# ADC_part3.net
KiCad netlist of a schematic drawn in Altium Designer
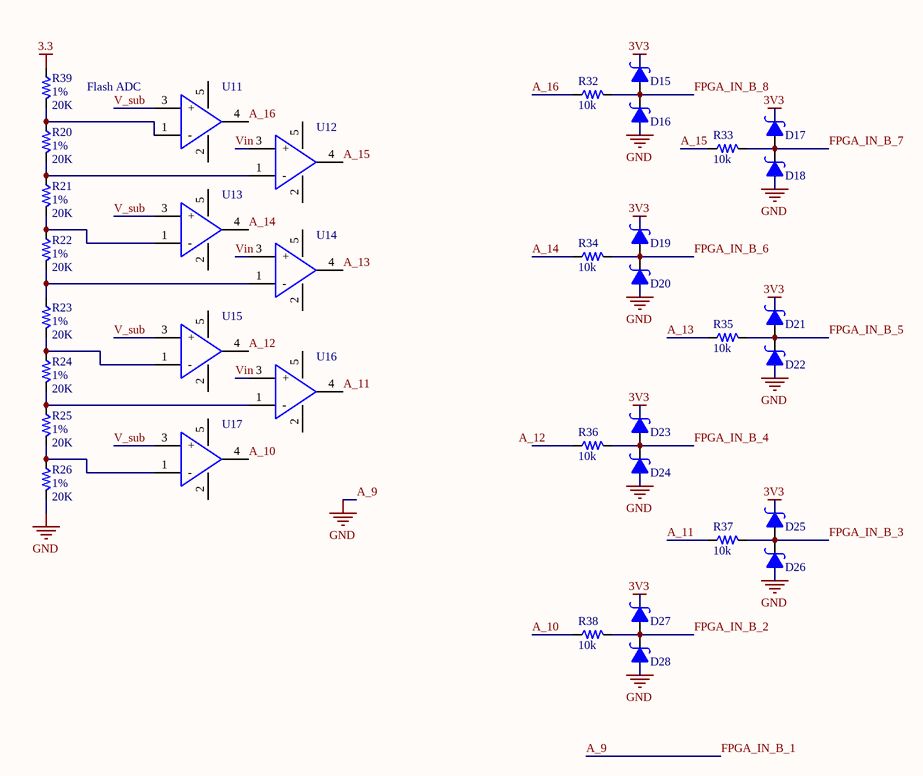
[diagram p0: ADC_part3.SchDoc]

(export (version "E")
  (design (tool "Eeschema 10.0.6"))
  (components
    (comp (ref "D15")
      (value "ONSEMI_MBRM110LT1G")
      (footprint "ON Semi Schottky Diode - MBRM110LT1G")
      (description "DIODE SCHOTTKY 10V 1A")
      (libsource (lib "ON Semi Schottky Diode") (part "ONSEMI_MBRM110LT1G"))
    )
    (comp (ref "D16")
      (value "ONSEMI_MBRM110LT1G")
      (footprint "ON Semi Schottky Diode - MBRM110LT1G")
      (description "DIODE SCHOTTKY 10V 1A")
      (libsource (lib "ON Semi Schottky Diode") (part "ONSEMI_MBRM110LT1G"))
    )
    (comp (ref "D17")
      (value "ONSEMI_MBRM110LT1G")
      (footprint "ON Semi Schottky Diode - MBRM110LT1G")
      (description "DIODE SCHOTTKY 10V 1A")
      (libsource (lib "ON Semi Schottky Diode") (part "ONSEMI_MBRM110LT1G"))
    )
    (comp (ref "D18")
      (value "ONSEMI_MBRM110LT1G")
      (footprint "ON Semi Schottky Diode - MBRM110LT1G")
      (description "DIODE SCHOTTKY 10V 1A")
      (libsource (lib "ON Semi Schottky Diode") (part "ONSEMI_MBRM110LT1G"))
    )
    (comp (ref "D19")
      (value "ONSEMI_MBRM110LT1G")
      (footprint "ON Semi Schottky Diode - MBRM110LT1G")
      (description "DIODE SCHOTTKY 10V 1A")
      (libsource (lib "ON Semi Schottky Diode") (part "ONSEMI_MBRM110LT1G"))
    )
    (comp (ref "D20")
      (value "ONSEMI_MBRM110LT1G")
      (footprint "ON Semi Schottky Diode - MBRM110LT1G")
      (description "DIODE SCHOTTKY 10V 1A")
      (libsource (lib "ON Semi Schottky Diode") (part "ONSEMI_MBRM110LT1G"))
    )
    (comp (ref "D21")
      (value "ONSEMI_MBRM110LT1G")
      (footprint "ON Semi Schottky Diode - MBRM110LT1G")
      (description "DIODE SCHOTTKY 10V 1A")
      (libsource (lib "ON Semi Schottky Diode") (part "ONSEMI_MBRM110LT1G"))
    )
    (comp (ref "D22")
      (value "ONSEMI_MBRM110LT1G")
      (footprint "ON Semi Schottky Diode - MBRM110LT1G")
      (description "DIODE SCHOTTKY 10V 1A")
      (libsource (lib "ON Semi Schottky Diode") (part "ONSEMI_MBRM110LT1G"))
    )
    (comp (ref "D23")
      (value "ONSEMI_MBRM110LT1G")
      (footprint "ON Semi Schottky Diode - MBRM110LT1G")
      (description "DIODE SCHOTTKY 10V 1A")
      (libsource (lib "ON Semi Schottky Diode") (part "ONSEMI_MBRM110LT1G"))
    )
    (comp (ref "D24")
      (value "ONSEMI_MBRM110LT1G")
      (footprint "ON Semi Schottky Diode - MBRM110LT1G")
      (description "DIODE SCHOTTKY 10V 1A")
      (libsource (lib "ON Semi Schottky Diode") (part "ONSEMI_MBRM110LT1G"))
    )
    (comp (ref "D25")
      (value "ONSEMI_MBRM110LT1G")
      (footprint "ON Semi Schottky Diode - MBRM110LT1G")
      (description "DIODE SCHOTTKY 10V 1A")
      (libsource (lib "ON Semi Schottky Diode") (part "ONSEMI_MBRM110LT1G"))
    )
    (comp (ref "D26")
      (value "ONSEMI_MBRM110LT1G")
      (footprint "ON Semi Schottky Diode - MBRM110LT1G")
      (description "DIODE SCHOTTKY 10V 1A")
      (libsource (lib "ON Semi Schottky Diode") (part "ONSEMI_MBRM110LT1G"))
    )
    (comp (ref "D27")
      (value "ONSEMI_MBRM110LT1G")
      (footprint "ON Semi Schottky Diode - MBRM110LT1G")
      (description "DIODE SCHOTTKY 10V 1A")
      (libsource (lib "ON Semi Schottky Diode") (part "ONSEMI_MBRM110LT1G"))
    )
    (comp (ref "D28")
      (value "ONSEMI_MBRM110LT1G")
      (footprint "ON Semi Schottky Diode - MBRM110LT1G")
      (description "DIODE SCHOTTKY 10V 1A")
      (libsource (lib "ON Semi Schottky Diode") (part "ONSEMI_MBRM110LT1G"))
    )
    (comp (ref "R20")
      (value "20K")
      (footprint "PCB_GENERIC_SMD_0603")
      (description "RES 0603 10K 1% 100mW")
      (fields
        (field (name "POWER") "100mW")
        (field (name "TOLERANCE") "1%")
        (field (name "Comment") "R060-00103-01")
      )
      (libsource (lib "RES") (part "R060-00103-01"))
    )
    (comp (ref "R21")
      (value "20K")
      (footprint "PCB_GENERIC_SMD_0603")
      (description "RES 0603 10K 1% 100mW")
      (fields
        (field (name "POWER") "100mW")
        (field (name "TOLERANCE") "1%")
        (field (name "Comment") "R060-00103-01")
      )
      (libsource (lib "RES") (part "R060-00103-01"))
    )
    (comp (ref "R22")
      (value "20K")
      (footprint "PCB_GENERIC_SMD_0603")
      (description "RES 0603 10K 1% 100mW")
      (fields
        (field (name "POWER") "100mW")
        (field (name "TOLERANCE") "1%")
        (field (name "Comment") "R060-00103-01")
      )
      (libsource (lib "RES") (part "R060-00103-01"))
    )
    (comp (ref "R23")
      (value "20K")
      (footprint "PCB_GENERIC_SMD_0603")
      (description "RES 0603 10K 1% 100mW")
      (fields
        (field (name "POWER") "100mW")
        (field (name "TOLERANCE") "1%")
        (field (name "Comment") "R060-00103-01")
      )
      (libsource (lib "RES") (part "R060-00103-01"))
    )
    (comp (ref "R24")
      (value "20K")
      (footprint "PCB_GENERIC_SMD_0603")
      (description "RES 0603 10K 1% 100mW")
      (fields
        (field (name "POWER") "100mW")
        (field (name "TOLERANCE") "1%")
        (field (name "Comment") "R060-00103-01")
      )
      (libsource (lib "RES") (part "R060-00103-01"))
    )
    (comp (ref "R25")
      (value "20K")
      (footprint "PCB_GENERIC_SMD_0603")
      (description "RES 0603 10K 1% 100mW")
      (fields
        (field (name "POWER") "100mW")
        (field (name "TOLERANCE") "1%")
        (field (name "Comment") "R060-00103-01")
      )
      (libsource (lib "RES") (part "R060-00103-01"))
    )
    (comp (ref "R26")
      (value "20K")
      (footprint "PCB_GENERIC_SMD_0603")
      (description "RES 0603 10K 1% 100mW")
      (fields
        (field (name "POWER") "100mW")
        (field (name "TOLERANCE") "1%")
        (field (name "Comment") "R060-00103-01")
      )
      (libsource (lib "RES") (part "R060-00103-01"))
    )
    (comp (ref "R32")
      (value "10k")
      (footprint "PCB_GENERIC_SMD_0603")
      (description "RES 0603 100ohm 5% 63mW")
      (fields (field (name "TOLERANCE") "5%") (field (name "POWER") "63mW"))
      (libsource (lib "RES") (part "R060-00101-05"))
    )
    (comp (ref "R33")
      (value "10k")
      (footprint "PCB_GENERIC_SMD_0603")
      (description "RES 0603 100ohm 5% 63mW")
      (fields (field (name "TOLERANCE") "5%") (field (name "POWER") "63mW"))
      (libsource (lib "RES") (part "R060-00101-05"))
    )
    (comp (ref "R34")
      (value "10k")
      (footprint "PCB_GENERIC_SMD_0603")
      (description "RES 0603 100ohm 5% 63mW")
      (fields (field (name "TOLERANCE") "5%") (field (name "POWER") "63mW"))
      (libsource (lib "RES") (part "R060-00101-05"))
    )
    (comp (ref "R35")
      (value "10k")
      (footprint "PCB_GENERIC_SMD_0603")
      (description "RES 0603 100ohm 5% 63mW")
      (fields (field (name "TOLERANCE") "5%") (field (name "POWER") "63mW"))
      (libsource (lib "RES") (part "R060-00101-05"))
    )
    (comp (ref "R36")
      (value "10k")
      (footprint "PCB_GENERIC_SMD_0603")
      (description "RES 0603 100ohm 5% 63mW")
      (fields (field (name "TOLERANCE") "5%") (field (name "POWER") "63mW"))
      (libsource (lib "RES") (part "R060-00101-05"))
    )
    (comp (ref "R37")
      (value "10k")
      (footprint "PCB_GENERIC_SMD_0603")
      (description "RES 0603 100ohm 5% 63mW")
      (fields (field (name "TOLERANCE") "5%") (field (name "POWER") "63mW"))
      (libsource (lib "RES") (part "R060-00101-05"))
    )
    (comp (ref "R38")
      (value "10k")
      (footprint "PCB_GENERIC_SMD_0603")
      (description "RES 0603 100ohm 5% 63mW")
      (fields (field (name "TOLERANCE") "5%") (field (name "POWER") "63mW"))
      (libsource (lib "RES") (part "R060-00101-05"))
    )
    (comp (ref "R39")
      (value "20K")
      (footprint "PCB_GENERIC_SMD_0603")
      (description "RES 0603 10K 1% 100mW")
      (fields
        (field (name "POWER") "100mW")
        (field (name "TOLERANCE") "1%")
        (field (name "Comment") "R060-00103-01")
      )
      (libsource (lib "RES") (part "R060-00103-01"))
    )
    (comp (ref "U11")
      (value "AP331A")
      (footprint "SOT95P285X130-5N")
      (description "Single Channel Comparator, Open Drain, SC-74A/SOT-753")
      (libsource (lib "Op_Amp") (part "AP331A"))
    )
    (comp (ref "U12")
      (value "AP331A")
      (footprint "SOT95P285X130-5N")
      (description "Single Channel Comparator, Open Drain, SC-74A/SOT-753")
      (libsource (lib "Op_Amp") (part "AP331A"))
    )
    (comp (ref "U13")
      (value "AP331A")
      (footprint "SOT95P285X130-5N")
      (description "Single Channel Comparator, Open Drain, SC-74A/SOT-753")
      (libsource (lib "Op_Amp") (part "AP331A"))
    )
    (comp (ref "U14")
      (value "AP331A")
      (footprint "SOT95P285X130-5N")
      (description "Single Channel Comparator, Open Drain, SC-74A/SOT-753")
      (libsource (lib "Op_Amp") (part "AP331A"))
    )
    (comp (ref "U15")
      (value "AP331A")
      (footprint "SOT95P285X130-5N")
      (description "Single Channel Comparator, Open Drain, SC-74A/SOT-753")
      (libsource (lib "Op_Amp") (part "AP331A"))
    )
    (comp (ref "U16")
      (value "AP331A")
      (footprint "SOT95P285X130-5N")
      (description "Single Channel Comparator, Open Drain, SC-74A/SOT-753")
      (libsource (lib "Op_Amp") (part "AP331A"))
    )
    (comp (ref "U17")
      (value "AP331A")
      (footprint "SOT95P285X130-5N")
      (description "Single Channel Comparator, Open Drain, SC-74A/SOT-753")
      (libsource (lib "Op_Amp") (part "AP331A"))
    )
  )
  (nets
    (net (code "1") (name "/A_10") (class "Default")
      (node (ref "R38") (pin "1") (pinfunction "1_1") (pintype "passive"))
      (node (ref "U17") (pin "4") (pinfunction "VOUT_4") (pintype "passive"))
    )
    (net (code "2") (name "/A_11") (class "Default")
      (node (ref "R37") (pin "1") (pinfunction "1_1") (pintype "passive"))
      (node (ref "U16") (pin "4") (pinfunction "VOUT_4") (pintype "passive"))
    )
    (net (code "3") (name "/A_12") (class "Default")
      (node (ref "U15") (pin "4") (pinfunction "VOUT_4") (pintype "passive"))
    )
    (net (code "4") (name "/A_13") (class "Default")
      (node (ref "R35") (pin "1") (pinfunction "1_1") (pintype "passive"))
      (node (ref "U14") (pin "4") (pinfunction "VOUT_4") (pintype "passive"))
    )
    (net (code "5") (name "/A_14") (class "Default")
      (node (ref "R34") (pin "1") (pinfunction "1_1") (pintype "passive"))
      (node (ref "U13") (pin "4") (pinfunction "VOUT_4") (pintype "passive"))
    )
    (net (code "6") (name "/A_15") (class "Default")
      (node (ref "R33") (pin "1") (pinfunction "1_1") (pintype "passive"))
      (node (ref "U12") (pin "4") (pinfunction "VOUT_4") (pintype "passive"))
    )
    (net (code "7") (name "/A_16") (class "Default")
      (node (ref "R32") (pin "1") (pinfunction "1_1") (pintype "passive"))
      (node (ref "U11") (pin "4") (pinfunction "VOUT_4") (pintype "passive"))
    )
    (net (code "8") (name "/FPGA_IN_B_2") (class "Default")
      (node (ref "D27") (pin "2") (pinfunction "2_2") (pintype "passive"))
      (node (ref "D28") (pin "1") (pinfunction "1_1") (pintype "passive"))
      (node (ref "R38") (pin "2") (pinfunction "2_2") (pintype "passive"))
    )
    (net (code "9") (name "/FPGA_IN_B_3") (class "Default")
      (node (ref "D25") (pin "2") (pinfunction "2_2") (pintype "passive"))
      (node (ref "D26") (pin "1") (pinfunction "1_1") (pintype "passive"))
      (node (ref "R37") (pin "2") (pinfunction "2_2") (pintype "passive"))
    )
    (net (code "10") (name "/FPGA_IN_B_4") (class "Default")
      (node (ref "D23") (pin "2") (pinfunction "2_2") (pintype "passive"))
      (node (ref "D24") (pin "1") (pinfunction "1_1") (pintype "passive"))
      (node (ref "R36") (pin "2") (pinfunction "2_2") (pintype "passive"))
    )
    (net (code "11") (name "/FPGA_IN_B_5") (class "Default")
      (node (ref "D21") (pin "2") (pinfunction "2_2") (pintype "passive"))
      (node (ref "D22") (pin "1") (pinfunction "1_1") (pintype "passive"))
      (node (ref "R35") (pin "2") (pinfunction "2_2") (pintype "passive"))
    )
    (net (code "12") (name "/FPGA_IN_B_6") (class "Default")
      (node (ref "D19") (pin "2") (pinfunction "2_2") (pintype "passive"))
      (node (ref "D20") (pin "1") (pinfunction "1_1") (pintype "passive"))
      (node (ref "R34") (pin "2") (pinfunction "2_2") (pintype "passive"))
    )
    (net (code "13") (name "/FPGA_IN_B_7") (class "Default")
      (node (ref "D17") (pin "2") (pinfunction "2_2") (pintype "passive"))
      (node (ref "D18") (pin "1") (pinfunction "1_1") (pintype "passive"))
      (node (ref "R33") (pin "2") (pinfunction "2_2") (pintype "passive"))
    )
    (net (code "14") (name "/FPGA_IN_B_8") (class "Default")
      (node (ref "D15") (pin "2") (pinfunction "2_2") (pintype "passive"))
      (node (ref "D16") (pin "1") (pinfunction "1_1") (pintype "passive"))
      (node (ref "R32") (pin "2") (pinfunction "2_2") (pintype "passive"))
    )
    (net (code "15") (name "/V_sub") (class "Default")
      (node (ref "U11") (pin "3") (pinfunction "+_3") (pintype "passive"))
      (node (ref "U13") (pin "3") (pinfunction "+_3") (pintype "passive"))
      (node (ref "U15") (pin "3") (pinfunction "+_3") (pintype "passive"))
      (node (ref "U17") (pin "3") (pinfunction "+_3") (pintype "passive"))
    )
    (net (code "16") (name "/Vin") (class "Default")
      (node (ref "U12") (pin "3") (pinfunction "+_3") (pintype "passive"))
      (node (ref "U14") (pin "3") (pinfunction "+_3") (pintype "passive"))
      (node (ref "U16") (pin "3") (pinfunction "+_3") (pintype "passive"))
    )
    (net (code "17") (name "3.3") (class "Default")
      (node (ref "R39") (pin "1") (pinfunction "1_1") (pintype "passive"))
    )
    (net (code "18") (name "3V3") (class "Default")
      (node (ref "D15") (pin "1") (pinfunction "1_1") (pintype "passive"))
      (node (ref "D17") (pin "1") (pinfunction "1_1") (pintype "passive"))
      (node (ref "D19") (pin "1") (pinfunction "1_1") (pintype "passive"))
      (node (ref "D21") (pin "1") (pinfunction "1_1") (pintype "passive"))
      (node (ref "D23") (pin "1") (pinfunction "1_1") (pintype "passive"))
      (node (ref "D25") (pin "1") (pinfunction "1_1") (pintype "passive"))
      (node (ref "D27") (pin "1") (pinfunction "1_1") (pintype "passive"))
    )
    (net (code "19") (name "GND") (class "Default")
      (node (ref "D16") (pin "2") (pinfunction "2_2") (pintype "passive"))
      (node (ref "D18") (pin "2") (pinfunction "2_2") (pintype "passive"))
      (node (ref "D20") (pin "2") (pinfunction "2_2") (pintype "passive"))
      (node (ref "D22") (pin "2") (pinfunction "2_2") (pintype "passive"))
      (node (ref "D24") (pin "2") (pinfunction "2_2") (pintype "passive"))
      (node (ref "D26") (pin "2") (pinfunction "2_2") (pintype "passive"))
      (node (ref "D28") (pin "2") (pinfunction "2_2") (pintype "passive"))
      (node (ref "R26") (pin "2") (pinfunction "2_2") (pintype "passive"))
    )
    (net (code "20") (name "Net-(U11--)") (class "Default")
      (node (ref "R20") (pin "1") (pinfunction "1_1") (pintype "passive"))
      (node (ref "R39") (pin "2") (pinfunction "2_2") (pintype "passive"))
      (node (ref "U11") (pin "1") (pinfunction "-_1") (pintype "passive"))
    )
    (net (code "21") (name "Net-(U12--)") (class "Default")
      (node (ref "R20") (pin "2") (pinfunction "2_2") (pintype "passive"))
      (node (ref "R21") (pin "1") (pinfunction "1_1") (pintype "passive"))
      (node (ref "U12") (pin "1") (pinfunction "-_1") (pintype "passive"))
    )
    (net (code "22") (name "Net-(U13--)") (class "Default")
      (node (ref "R21") (pin "2") (pinfunction "2_2") (pintype "passive"))
      (node (ref "R22") (pin "1") (pinfunction "1_1") (pintype "passive"))
      (node (ref "U13") (pin "1") (pinfunction "-_1") (pintype "passive"))
    )
    (net (code "23") (name "Net-(U14--)") (class "Default")
      (node (ref "R22") (pin "2") (pinfunction "2_2") (pintype "passive"))
      (node (ref "R23") (pin "1") (pinfunction "1_1") (pintype "passive"))
      (node (ref "U14") (pin "1") (pinfunction "-_1") (pintype "passive"))
    )
    (net (code "24") (name "Net-(U15--)") (class "Default")
      (node (ref "R23") (pin "2") (pinfunction "2_2") (pintype "passive"))
      (node (ref "R24") (pin "1") (pinfunction "1_1") (pintype "passive"))
      (node (ref "U15") (pin "1") (pinfunction "-_1") (pintype "passive"))
    )
    (net (code "25") (name "Net-(U16--)") (class "Default")
      (node (ref "R24") (pin "2") (pinfunction "2_2") (pintype "passive"))
      (node (ref "R25") (pin "1") (pinfunction "1_1") (pintype "passive"))
      (node (ref "U16") (pin "1") (pinfunction "-_1") (pintype "passive"))
    )
    (net (code "26") (name "Net-(U17--)") (class "Default")
      (node (ref "R25") (pin "2") (pinfunction "2_2") (pintype "passive"))
      (node (ref "R26") (pin "1") (pinfunction "1_1") (pintype "passive"))
      (node (ref "U17") (pin "1") (pinfunction "-_1") (pintype "passive"))
    )
    (net (code "27") (name "unconnected-(R36-Pad1)") (class "Default")
      (node (ref "R36") (pin "1") (pinfunction "1_1") (pintype "passive"))
    )
    (net (code "28") (name "unconnected-(U11-GND-Pad2)") (class "Default")
      (node (ref "U11") (pin "2") (pinfunction "GND_2") (pintype "passive"))
    )
    (net (code "29") (name "unconnected-(U11-VCC-Pad5)") (class "Default")
      (node (ref "U11") (pin "5") (pinfunction "VCC_5") (pintype "passive"))
    )
    (net (code "30") (name "unconnected-(U12-GND-Pad2)") (class "Default")
      (node (ref "U12") (pin "2") (pinfunction "GND_2") (pintype "passive"))
    )
    (net (code "31") (name "unconnected-(U12-VCC-Pad5)") (class "Default")
      (node (ref "U12") (pin "5") (pinfunction "VCC_5") (pintype "passive"))
    )
    (net (code "32") (name "unconnected-(U13-GND-Pad2)") (class "Default")
      (node (ref "U13") (pin "2") (pinfunction "GND_2") (pintype "passive"))
    )
    (net (code "33") (name "unconnected-(U13-VCC-Pad5)") (class "Default")
      (node (ref "U13") (pin "5") (pinfunction "VCC_5") (pintype "passive"))
    )
    (net (code "34") (name "unconnected-(U14-GND-Pad2)") (class "Default")
      (node (ref "U14") (pin "2") (pinfunction "GND_2") (pintype "passive"))
    )
    (net (code "35") (name "unconnected-(U14-VCC-Pad5)") (class "Default")
      (node (ref "U14") (pin "5") (pinfunction "VCC_5") (pintype "passive"))
    )
    (net (code "36") (name "unconnected-(U15-GND-Pad2)") (class "Default")
      (node (ref "U15") (pin "2") (pinfunction "GND_2") (pintype "passive"))
    )
    (net (code "37") (name "unconnected-(U15-VCC-Pad5)") (class "Default")
      (node (ref "U15") (pin "5") (pinfunction "VCC_5") (pintype "passive"))
    )
    (net (code "38") (name "unconnected-(U16-GND-Pad2)") (class "Default")
      (node (ref "U16") (pin "2") (pinfunction "GND_2") (pintype "passive"))
    )
    (net (code "39") (name "unconnected-(U16-VCC-Pad5)") (class "Default")
      (node (ref "U16") (pin "5") (pinfunction "VCC_5") (pintype "passive"))
    )
    (net (code "40") (name "unconnected-(U17-GND-Pad2)") (class "Default")
      (node (ref "U17") (pin "2") (pinfunction "GND_2") (pintype "passive"))
    )
    (net (code "41") (name "unconnected-(U17-VCC-Pad5)") (class "Default")
      (node (ref "U17") (pin "5") (pinfunction "VCC_5") (pintype "passive"))
    )
  )
)
